# PROTECTION_AND_POWER_SUPPLY.net
KiCad netlist of a schematic drawn in Altium Designer
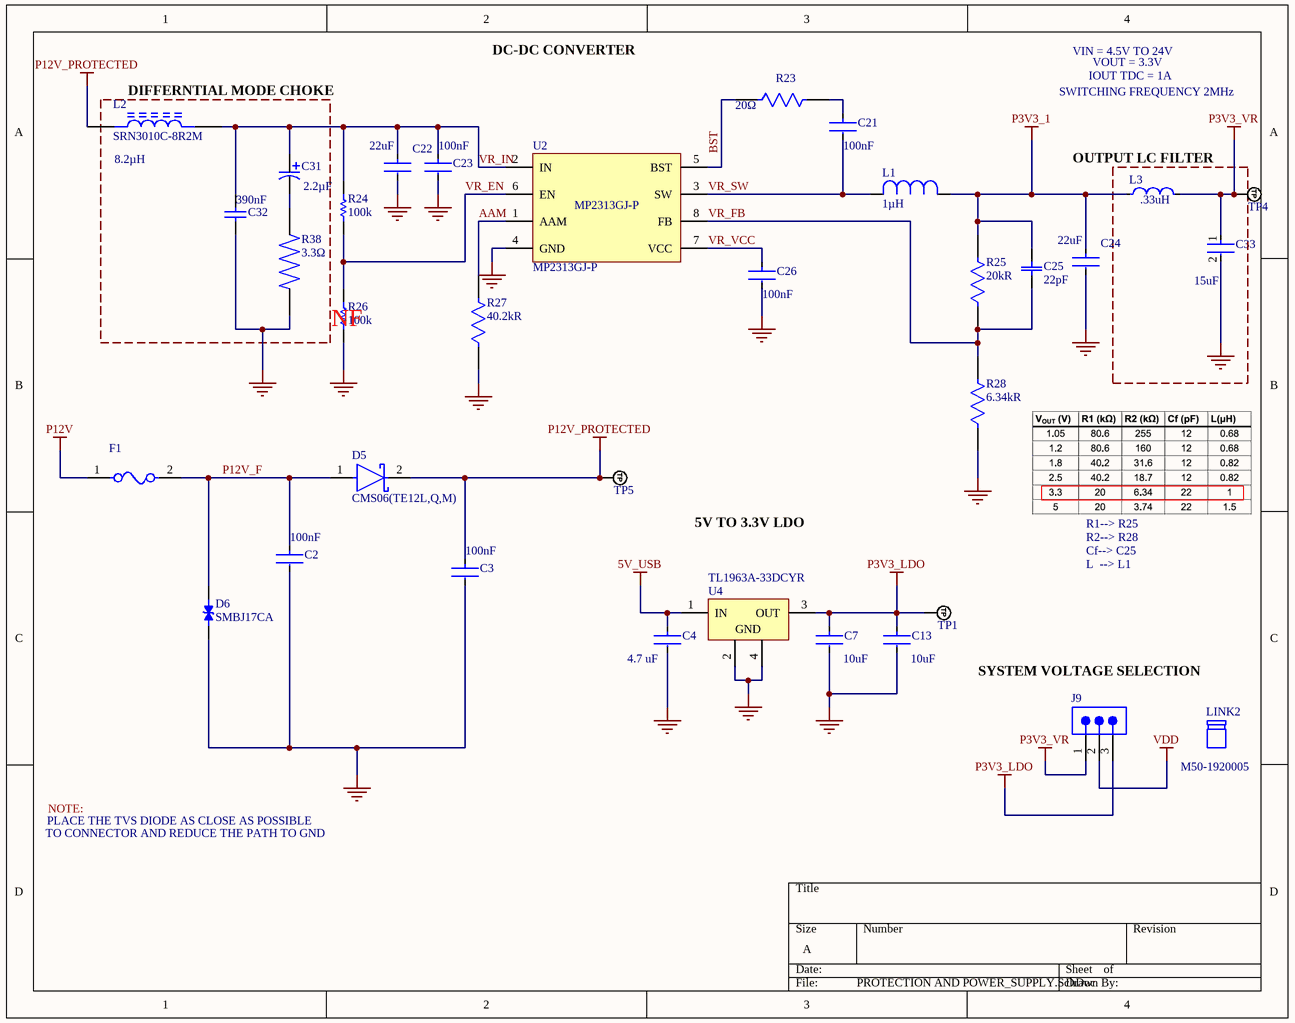
[diagram p0: PROTECTION AND POWER_SUPPLY.SchDoc]

(export (version "E")
  (design (tool "Eeschema 10.0.6"))
  (components
    (comp (ref "C2")
      (value "TMK105B7104KVHF")
      (footprint "FP-0402-L_1_0_0_05-W_0_5-MFG")
      (description "0.1 µF ±10% 25V Condensatori ceramici X7R 0402 (1005 metrico)")
      (fields (field (name "CAPACITANCE") "100nF") (field (name "TOLERANCE") "10%"))
      (libsource (lib "") (part "b4654b650e69147ec39a6b967a45e02_1"))
    )
    (comp (ref "C3")
      (value "TMK105B7104KVHF")
      (footprint "FP-0402-L_1_0_0_05-W_0_5-MFG")
      (description "0.1 µF ±10% 25V Condensatori ceramici X7R 0402 (1005 metrico)")
      (fields (field (name "CAPACITANCE") "100nF") (field (name "TOLERANCE") "10%"))
      (libsource (lib "") (part "b4654b650e69147ec39a6b967a45e02_1"))
    )
    (comp (ref "C4")
      (value "CC0603KRX5R7BB475")
      (footprint "FP-CC0603-DA-MFG")
      (description "CAP CER 4.7UF 16V X5R 0603")
      (fields
        (field (name "MANUFACTURER") "YAGEO")
        (field (name "VOLTAGE") "16 V")
        (field (name "CAPACITANCE") "4.7 uF")
      )
      (libsource (lib "Altium Content Vault") (part "11868f565c42a9108669ba33697ecf6"))
    )
    (comp (ref "C7")
      (value "EMK212BB7106KG-T")
      (footprint "FP-0805-L_2_0_0_2-W_1_25-MFG")
      (description "CAP CER 10UF 16V X7R 0805")
      (fields (field (name "TOLERANCE") "10%") (field (name "CAPACITANCE") "10uF"))
      (libsource (lib "") (part "b4654b650e69147ec39a6b967a45e02_1"))
    )
    (comp (ref "C13")
      (value "EMK212BB7106KG-T")
      (footprint "FP-0805-L_2_0_0_2-W_1_25-MFG")
      (description "CAP CER 10UF 16V X7R 0805")
      (fields (field (name "TOLERANCE") "10%") (field (name "CAPACITANCE") "10uF"))
      (libsource (lib "") (part "b4654b650e69147ec39a6b967a45e02_1"))
    )
    (comp (ref "C21")
      (value "TMK105B7104KVHF")
      (footprint "FP-0402-L_1_0_0_05-W_0_5-MFG")
      (description "None")
      (fields (field (name "CAPACITANCE") "100nF") (field (name "TOLERANCE") "10%"))
      (libsource (lib "") (part "b4654b650e69147ec39a6b967a45e02_1"))
    )
    (comp (ref "C22")
      (value "TMK325B7226KMHP")
      (footprint "FP-1210-L_3_2_0_3-W_2_5_0-MFG")
      (description "CAP CER 22UF 25V X7R 1210")
      (fields (field (name "TOLERANCE") "10%") (field (name "CAPACITANCE") "22uF"))
      (libsource (lib "Altium Content Vault") (part "02cd4be3c70576c341d710602a673aa"))
    )
    (comp (ref "C23")
      (value "TMK105B7104KVHF")
      (footprint "FP-0402-L_1_0_0_05-W_0_5-MFG")
      (description "0.1 µF ±10% 25V Condensatori ceramici X7R 0402 (1005 metrico)")
      (fields (field (name "CAPACITANCE") "100nF") (field (name "TOLERANCE") "10%"))
      (libsource (lib "") (part "b4654b650e69147ec39a6b967a45e02_1"))
    )
    (comp (ref "C24")
      (value "TMK325B7226KMHP")
      (footprint "FP-1210-L_3_2_0_3-W_2_5_0-MFG")
      (description "CAP CER 22UF 25V X7R 1210")
      (fields (field (name "TOLERANCE") "10%") (field (name "CAPACITANCE") "22uF"))
      (libsource (lib "Altium Content Vault") (part "02cd4be3c70576c341d710602a673aa"))
    )
    (comp (ref "C25")
      (value "22pF")
      (footprint "CAP_0805")
      (description "Cap Ceramic 22pF 16V C0G 10% 0805 T/R")
      (fields
        (field (name "MANUFACTURER") "KYOCERA AVX")
        (field (name "MANUFACTURER PART NUMBER") "0805YA220K4T2A")
      )
      (libsource (lib "F1_MODULE") (part "0805YA220K4T2A"))
    )
    (comp (ref "C26")
      (value "TMK105B7104KVHF")
      (footprint "FP-0402-L_1_0_0_05-W_0_5-MFG")
      (description "0.1 µF ±10% 25V Condensatori ceramici X7R 0402 (1005 metrico)")
      (fields (field (name "CAPACITANCE") "100nF") (field (name "TOLERANCE") "10%"))
      (libsource (lib "") (part "b4654b650e69147ec39a6b967a45e02_1"))
    )
    (comp (ref "C31")
      (value "2.2µF")
      (footprint "CAP_EEE_B_PAN")
      (description "Radial Can - SMD ALUMINUM ELECTROLYTIC CAPACITOR S 50V 2.2muF ±20% 0.157Dia 4.00mm")
      (fields
        (field (name "MANUFACTURER") "Panasonic")
        (field (name "MANUFACTURER PART NUMBER") "EEE-1HA2R2SR")
      )
      (libsource (lib "F1_MODULE") (part "EEE-1HA2R2SR"))
    )
    (comp (ref "C32")
      (value "390nF")
      (footprint "CAPC0805(2012)110_N")
      (description "CAP 390nF 50V ±10% 0805 (2012 Metric) Thickness 1.1mm SMD")
      (fields (field (name "TOLERANCE") "Â±10%") (field (name "Comment") "C0805C394K5RACTU"))
      (libsource (lib "Altium Content Vault") (part "CAP"))
    )
    (comp (ref "C33")
      (value "C2012X5R1E156M125AC")
      (footprint "FP-C2012-125-0_2-MFG")
      (description "Multilayer Ceramic Capacitors 15μF ±20% 25V X5R SMD 0805")
      (fields (field (name "CAPACITANCE") "15uF") (field (name "TOLERANCE") "20%"))
      (libsource (lib "Altium Content Vault") (part "b4654b650e69147ec39a6b967a45e02"))
    )
    (comp (ref "D5")
      (value "CMS06(TE12L,Q,M)")
      (footprint "FP-M-FLAT-MFG")
      (description "DIODE SCHOTTKY 30V 2A MFLAT")
      (libsource (lib "Altium Content Vault") (part "360ad2f4ac25a952324d13796385471"))
    )
    (comp (ref "D6")
      (value "SMBJ17CA")
      (footprint "SMBJSeries_LTF")
      (description "DO-214AA SMB SMBJ Surface Mount 1 Zener Tvs Diode 18.9V 21.7A 600W -55C~150C TJ")
      (fields (field (name "MANUFACTURER") "Taiwan Semiconductor"))
      (libsource (lib "F1_MODULE") (part "SMBJ17CA"))
    )
    (comp (ref "F1")
      (value "MINISMDC110F/24-2")
      (footprint "FP-MINISMDC110F-24-2-MFG")
      (description "PTC RESET FUSE 24V 1.1A 1812")
      (fields
        (field (name "OCTOPART") "https://octopart.com/minismdc110f%2F24-2-littelfuse-74215018")
        (field (name "MANUFACTURER") "Littelfuse")
      )
      (libsource (lib "Altium Content Vault") (part "5bcf9b9f640e542cf0359d10258e979"))
    )
    (comp (ref "J9")
      (value "61300311121")
      (footprint "61300311121")
      (description "CONN HEADER VERT 3POS 2.54MM")
      (libsource (lib "Altium Content Vault") (part "Header_Male_1R_03P"))
    )
    (comp (ref "L1")
      (value "1µH")
      (footprint "IND_MDMK2020T1R0MM_TAY")
      (description "Inductor Power Shielded Wirewound 1uH 20% 1MHz Metal 1.9A 0.064Ohm DCR Automotive T/R")
      (fields
        (field (name "MANUFACTURER") "Taiyo Yuden")
        (field (name "MANUFACTURER PART NUMBER") "MDMK2020T1R0MMV")
      )
      (libsource (lib "F1_MODULE") (part "MDMK2020T1R0MMV"))
    )
    (comp (ref "L2")
      (value "SRN3010C-8R2M")
      (footprint "IND_SRN3010C-8R2M")
      (description "General Purpose Inductor, 8.2uH, 20%, 1 Element, Ferrite-Core, SMD, 1212")
      (fields
        (field (name "MANUFACTURER") "Bourns")
        (field (name "ALTIUM_VALUE") "8.2µH")
        (field (name "TOLERANCE") "20%")
      )
      (libsource (lib "F1_MODULE") (part "SRN3010C-8R2M"))
    )
    (comp (ref "L3")
      (value "DFE201210U-R33M=P2")
      (footprint "FP-DFE201210U-MFG")
      (description "FIXED IND .33UH 3.4A 31MOHM")
      (fields (field (name "INDUCTANCE VALUE") ".33uH"))
      (libsource (lib "Altium Content Vault") (part "725321dda6339637d4d059423bc1c3c"))
    )
    (comp (ref "LINK2")
      (value "M50-1920005")
      (description "CONN SHUNT 1.27MM RED")
      (fields (field (name "MANUFACTURER") "Harwin") (field (name "LCSC PART NUMBER") "C6985646"))
      (libsource (lib "Schlib") (part "M50-1920005"))
    )
    (comp (ref "R23")
      (value "RT0402FRE0720RL")
      (footprint "FP-RT0402-MFG")
      (description "RES SMD 20 OHM 1% 1/16W 0402")
      (fields
        (field (name "RESISTANCE") "20Ω")
        (field (name "MANUFACTURER") "Yageo")
        (field (name "OCTOPART") "https://octopart.com/rt0402fre0720rl-yageo-1278881")
      )
      (libsource (lib "Altium Content Vault") (part "1029c3af85768c4190bb7ad29bc67b5"))
    )
    (comp (ref "R24")
      (value "100k")
      (footprint "RESC1005X40X25NL05T10")
      (description "100 kOhms ±1% 0.063W, 1/16W Chip Resistor 0402 (1005 Metric) Moisture Resistant Thick Film")
      (fields (field (name "PART NUMBER") "RC0402FR-07100KL") (field (name "MANUFACTURER") "Yageo / Phycomp"))
      (libsource (lib "Altium Content Vault") (part "RES"))
    )
    (comp (ref "R25")
      (value "AF0402JR-0720KL")
      (footprint "FP-AF0402-MFG")
      (description "Anti-Sulfurated Chip Resistors Automotive Grade 20kΩ 5% 100ppm/°C 0402")
      (fields (field (name "TOLERANCE") "5%") (field (name "RESISTANCE") "20kR"))
      (libsource (lib "Altium Content Vault") (part "1029c3af85768c4190bb7ad29bc67b5"))
    )
    (comp (ref "R26")
      (value "100k")
      (footprint "RESC1005X40X25NL05T10")
      (description "100 kOhms ±1% 0.063W, 1/16W Chip Resistor 0402 (1005 Metric) Moisture Resistant Thick Film")
      (fields (field (name "PART NUMBER") "RC0402FR-07100KL") (field (name "MANUFACTURER") "Yageo / Phycomp"))
      (libsource (lib "Altium Content Vault") (part "RES"))
    )
    (comp (ref "R27")
      (value "AF0402FR-0740K2L")
      (footprint "FP-AF0402-MFG")
      (description "Anti-Sulfurated Chip Resistors Automotive Grade 40.2kΩ 1% 100ppm/°C 0402")
      (fields (field (name "RESISTANCE") "40.2kR") (field (name "TOLERANCE") "1%"))
      (libsource (lib "Altium Content Vault") (part "1029c3af85768c4190bb7ad29bc67b5"))
    )
    (comp (ref "R28")
      (value "MCT06030C6341FP500")
      (footprint "FP-MCT0603-MFG")
      (description "RES SMD 100 OHM 1% 1/8W 0603")
      (fields (field (name "TOLERANCE") "1%") (field (name "RESISTANCE") "6.34kR"))
      (libsource (lib "Altium Content Vault") (part "1029c3af85768c4190bb7ad29bc67b5"))
    )
    (comp (ref "R38")
      (value "3.3Ω")
      (footprint "RESC6331X80N")
      (description "Res Thick Film 2512 3.3 Ohm 5% 2W ±200ppm/C Pad SMD T/R")
      (fields
        (field (name "MANUFACTURER") "Bourns")
        (field (name "MANUFACTURER PART NUMBER") "CRM2512-JW-3R3ELF")
      )
      (libsource (lib "F1_MODULE") (part "CRM2512-JW-3R3ELF"))
    )
    (comp (ref "TP1")
      (value "TP_NOBOM")
      (footprint "PAD_RND_1MM")
      (description "Test Point Round 1mm (NO BOM)")
      (libsource (lib "Schematic-Lib-PhilsLab") (part "TEST_POINT_RND_1MM"))
    )
    (comp (ref "TP4")
      (value "TP_NOBOM")
      (footprint "PAD_RND_1MM")
      (description "Test Point Round 1mm (NO BOM)")
      (libsource (lib "Schematic-Lib-PhilsLab") (part "TEST_POINT_RND_1MM"))
    )
    (comp (ref "TP5")
      (value "TP_NOBOM")
      (footprint "PAD_RND_1MM")
      (description "Test Point Round 1mm (NO BOM)")
      (libsource (lib "Schematic-Lib-PhilsLab") (part "TEST_POINT_RND_1MM"))
    )
    (comp (ref "U2")
      (value "MP2313GJ-P")
      (footprint "TSOT23-8_MP2313_MNP")
      (description "Switching Voltage Regulators High Effic 1A,24V, 2MHz Syn StepDw Conv")
      (libsource (lib "F1_MODULE") (part "MP2313GJ-P"))
    )
    (comp (ref "U4")
      (value "TL1963A-33DCYR")
      (footprint "DCY0004A_N")
      (fields (field (name "MANUFACTURER") "Texas Instruments"))
      (libsource (lib "Altium Content Vault") (part "TI-TL1963A-XXDCY4"))
    )
  )
  (nets
    (net (code "1") (name "/AAM") (class "Default")
      (node (ref "R27") (pin "2") (pinfunction "2_2") (pintype "passive"))
      (node (ref "U2") (pin "1") (pinfunction "AAM_1") (pintype "passive"))
    )
    (net (code "2") (name "/BST") (class "Default")
      (node (ref "R23") (pin "1") (pinfunction "1_1") (pintype "passive"))
      (node (ref "U2") (pin "5") (pinfunction "BST_5") (pintype "passive"))
    )
    (net (code "3") (name "/P12V_F") (class "Default")
      (node (ref "C2") (pin "1") (pinfunction "1_1") (pintype "passive"))
      (node (ref "D5") (pin "1") (pinfunction "A_1") (pintype "passive"))
      (node (ref "D6") (pin "2") (pinfunction "2_2") (pintype "passive"))
      (node (ref "F1") (pin "2") (pinfunction "2_2") (pintype "passive"))
    )
    (net (code "4") (name "/VR_EN") (class "Default")
      (node (ref "R24") (pin "1") (pinfunction "1_1") (pintype "passive"))
      (node (ref "R26") (pin "2") (pinfunction "2_2") (pintype "passive"))
      (node (ref "U2") (pin "6") (pinfunction "EN_6") (pintype "passive"))
    )
    (net (code "5") (name "/VR_FB") (class "Default")
      (node (ref "C25") (pin "1") (pinfunction "1_1") (pintype "passive"))
      (node (ref "R25") (pin "1") (pinfunction "1_1") (pintype "passive"))
      (node (ref "R28") (pin "2") (pinfunction "2_2") (pintype "passive"))
      (node (ref "U2") (pin "8") (pinfunction "FB_8") (pintype "passive"))
    )
    (net (code "6") (name "/VR_IN") (class "Default")
      (node (ref "C22") (pin "1") (pinfunction "1_1") (pintype "passive"))
      (node (ref "C23") (pin "1") (pinfunction "1_1") (pintype "passive"))
      (node (ref "C31") (pin "1") (pinfunction "1_1") (pintype "passive"))
      (node (ref "C32") (pin "2") (pinfunction "2_2") (pintype "passive"))
      (node (ref "L2") (pin "2") (pinfunction "2_2") (pintype "passive"))
      (node (ref "R24") (pin "2") (pinfunction "2_2") (pintype "passive"))
      (node (ref "U2") (pin "2") (pinfunction "IN_2") (pintype "passive"))
    )
    (net (code "7") (name "/VR_SW") (class "Default")
      (node (ref "C21") (pin "2") (pinfunction "2_2") (pintype "passive"))
      (node (ref "L1") (pin "2") (pinfunction "2_2") (pintype "passive"))
      (node (ref "U2") (pin "3") (pinfunction "SW_3") (pintype "passive"))
    )
    (net (code "8") (name "/VR_VCC") (class "Default")
      (node (ref "C26") (pin "1") (pinfunction "1_1") (pintype "passive"))
      (node (ref "U2") (pin "7") (pinfunction "VCC_7") (pintype "passive"))
    )
    (net (code "9") (name "5V_USB") (class "Default")
      (node (ref "C4") (pin "1") (pinfunction "1_1") (pintype "passive"))
      (node (ref "U4") (pin "1") (pinfunction "IN_1") (pintype "power_in"))
    )
    (net (code "10") (name "GND") (class "Default")
      (node (ref "C13") (pin "2") (pinfunction "2_2") (pintype "passive"))
      (node (ref "C2") (pin "2") (pinfunction "2_2") (pintype "passive"))
      (node (ref "C22") (pin "2") (pinfunction "2_2") (pintype "passive"))
      (node (ref "C23") (pin "2") (pinfunction "2_2") (pintype "passive"))
      (node (ref "C24") (pin "2") (pinfunction "2_2") (pintype "passive"))
      (node (ref "C26") (pin "2") (pinfunction "2_2") (pintype "passive"))
      (node (ref "C3") (pin "2") (pinfunction "2_2") (pintype "passive"))
      (node (ref "C32") (pin "1") (pinfunction "1_1") (pintype "passive"))
      (node (ref "C33") (pin "2") (pinfunction "2_2") (pintype "passive"))
      (node (ref "C4") (pin "2") (pinfunction "2_2") (pintype "passive"))
      (node (ref "C7") (pin "2") (pinfunction "2_2") (pintype "passive"))
      (node (ref "D6") (pin "1") (pinfunction "1_1") (pintype "passive"))
      (node (ref "R26") (pin "1") (pinfunction "1_1") (pintype "passive"))
      (node (ref "R27") (pin "1") (pinfunction "1_1") (pintype "passive"))
      (node (ref "R28") (pin "1") (pinfunction "1_1") (pintype "passive"))
      (node (ref "R38") (pin "2") (pinfunction "2_2") (pintype "passive"))
      (node (ref "U2") (pin "4") (pinfunction "GND_4") (pintype "passive"))
      (node (ref "U4") (pin "2") (pinfunction "GND_2") (pintype "power_in"))
      (node (ref "U4") (pin "4") (pinfunction "GND_4") (pintype "power_in"))
    )
    (net (code "11") (name "Net-(C21-Pad1)") (class "Default")
      (node (ref "C21") (pin "1") (pinfunction "1_1") (pintype "passive"))
      (node (ref "R23") (pin "2") (pinfunction "2_2") (pintype "passive"))
    )
    (net (code "12") (name "Net-(C31-Pad2)") (class "Default")
      (node (ref "C31") (pin "2") (pinfunction "2_2") (pintype "passive"))
      (node (ref "R38") (pin "1") (pinfunction "1_1") (pintype "passive"))
    )
    (net (code "13") (name "P3V3_1") (class "Default")
      (node (ref "C24") (pin "1") (pinfunction "1_1") (pintype "passive"))
      (node (ref "C25") (pin "2") (pinfunction "2_2") (pintype "passive"))
      (node (ref "L1") (pin "1") (pinfunction "1_1") (pintype "passive"))
      (node (ref "L3") (pin "1") (pinfunction "1_1") (pintype "passive"))
      (node (ref "R25") (pin "2") (pinfunction "2_2") (pintype "passive"))
    )
    (net (code "14") (name "P3V3_LDO") (class "Default")
      (node (ref "C13") (pin "1") (pinfunction "1_1") (pintype "passive"))
      (node (ref "C7") (pin "1") (pinfunction "1_1") (pintype "passive"))
      (node (ref "J9") (pin "3") (pinfunction "3_3") (pintype "passive"))
      (node (ref "TP1") (pin "1") (pinfunction "TP_1") (pintype "passive"))
      (node (ref "U4") (pin "3") (pinfunction "OUT_3") (pintype "power_in"))
    )
    (net (code "15") (name "P3V3_VR") (class "Default")
      (node (ref "C33") (pin "1") (pinfunction "1_1") (pintype "passive"))
      (node (ref "J9") (pin "1") (pinfunction "1_1") (pintype "passive"))
      (node (ref "L3") (pin "2") (pinfunction "2_2") (pintype "passive"))
      (node (ref "TP4") (pin "1") (pinfunction "TP_1") (pintype "passive"))
    )
    (net (code "16") (name "P12V") (class "Default")
      (node (ref "F1") (pin "1") (pinfunction "1_1") (pintype "passive"))
    )
    (net (code "17") (name "P12V_PROTECTED") (class "Default")
      (node (ref "C3") (pin "1") (pinfunction "1_1") (pintype "passive"))
      (node (ref "D5") (pin "2") (pinfunction "C_2") (pintype "passive"))
      (node (ref "L2") (pin "1") (pinfunction "1_1") (pintype "passive"))
      (node (ref "TP5") (pin "1") (pinfunction "TP_1") (pintype "passive"))
    )
    (net (code "18") (name "VDD") (class "Default")
      (node (ref "J9") (pin "2") (pinfunction "2_2") (pintype "passive"))
    )
  )
)
